# esp8266.net
KiCad netlist of a schematic drawn in EAGLE
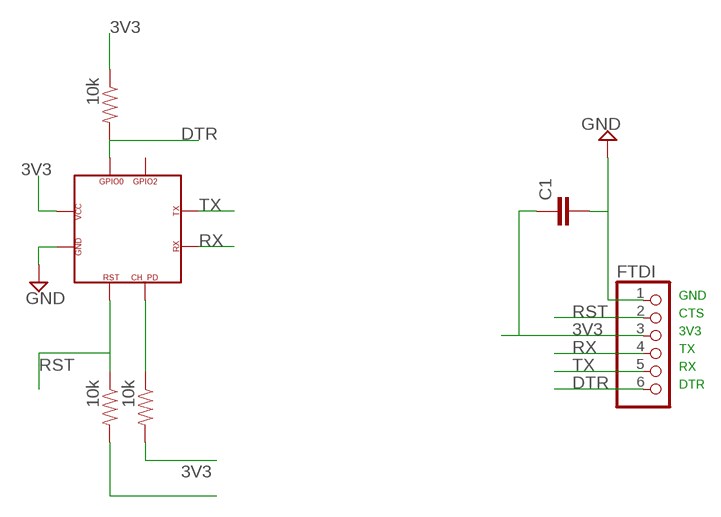
[diagram p0: schematic, sheet 1]

(export (version "E")
  (design (tool "Eeschema 10.0.6"))
  (components
    (comp (ref "C1")
      (value "CAPEZ")
      (footprint "eagle-import:CAP-PTH-SMALLEZ")
      (libsource (lib "eagle-import") (part "CAPEZ"))
    )
    (comp (ref "FTDI")
      (value "PINHD-1X6/90")
      (footprint "eagle-import:1X06_90")
      (libsource (lib "eagle-import") (part "PINHD-1X6/90"))
    )
    (comp (ref "R1")
      (value "10k")
      (footprint "eagle-import:AXIAL-0.5")
      (libsource (lib "eagle-import") (part "RESISTORPTH-1/2W"))
    )
    (comp (ref "R2")
      (value "10k")
      (footprint "eagle-import:AXIAL-0.5")
      (libsource (lib "eagle-import") (part "RESISTORPTH-1/2W"))
    )
    (comp (ref "R3")
      (value "10k")
      (footprint "eagle-import:AXIAL-0.5")
      (libsource (lib "eagle-import") (part "RESISTORPTH-1/2W"))
    )
    (comp (ref "U$1")
      (value "ESP-01")
      (footprint "eagle-import:ESP-01")
      (libsource (lib "eagle-import") (part "ESP-01"))
    )
  )
  (nets
    (net (code "1") (name "/3V3") (class "Default")
      (node (ref "C1") (pin "1") (pinfunction "1_1") (pintype "passive"))
      (node (ref "FTDI") (pin "3") (pinfunction "3_3") (pintype "passive"))
      (node (ref "R1") (pin "P$1") (pinfunction "1_P$1") (pintype "passive"))
      (node (ref "R2") (pin "P$2") (pinfunction "2_P$2") (pintype "passive"))
      (node (ref "R3") (pin "P$2") (pinfunction "2_P$2") (pintype "passive"))
      (node (ref "U$1") (pin "VCC") (pinfunction "VCC_VCC") (pintype "bidirectional"))
    )
    (net (code "2") (name "/DTR") (class "Default")
      (node (ref "FTDI") (pin "6") (pinfunction "6_6") (pintype "passive"))
      (node (ref "R1") (pin "P$2") (pinfunction "2_P$2") (pintype "passive"))
      (node (ref "U$1") (pin "GPIO0") (pinfunction "GPIO0_GPIO0") (pintype "bidirectional"))
    )
    (net (code "3") (name "/RST") (class "Default")
      (node (ref "FTDI") (pin "2") (pinfunction "2_2") (pintype "passive"))
      (node (ref "R3") (pin "P$1") (pinfunction "1_P$1") (pintype "passive"))
      (node (ref "U$1") (pin "RST") (pinfunction "RST_RST") (pintype "bidirectional"))
    )
    (net (code "4") (name "/RX") (class "Default")
      (node (ref "FTDI") (pin "4") (pinfunction "4_4") (pintype "passive"))
      (node (ref "U$1") (pin "RXD") (pinfunction "RX_RXD") (pintype "bidirectional"))
    )
    (net (code "5") (name "/TX") (class "Default")
      (node (ref "FTDI") (pin "5") (pinfunction "5_5") (pintype "passive"))
      (node (ref "U$1") (pin "TXD") (pinfunction "TX_TXD") (pintype "bidirectional"))
    )
    (net (code "6") (name "GND") (class "Default")
      (node (ref "C1") (pin "2") (pinfunction "2_2") (pintype "passive"))
      (node (ref "FTDI") (pin "1") (pinfunction "1_1") (pintype "passive"))
      (node (ref "U$1") (pin "GND") (pinfunction "GND_GND") (pintype "bidirectional"))
    )
    (net (code "7") (name "Net-(R2-1)") (class "Default")
      (node (ref "R2") (pin "P$1") (pinfunction "1_P$1") (pintype "passive"))
      (node (ref "U$1") (pin "CH_PD") (pinfunction "CP_PD_CH_PD") (pintype "bidirectional"))
    )
    (net (code "8") (name "unconnected-(U$1-PadGPIO2)") (class "Default")
      (node (ref "U$1") (pin "GPIO2") (pinfunction "GPIO2_GPIO2") (pintype "bidirectional"))
    )
  )
)
